# DriverIC.net
KiCad netlist of a schematic drawn in Altium Designer
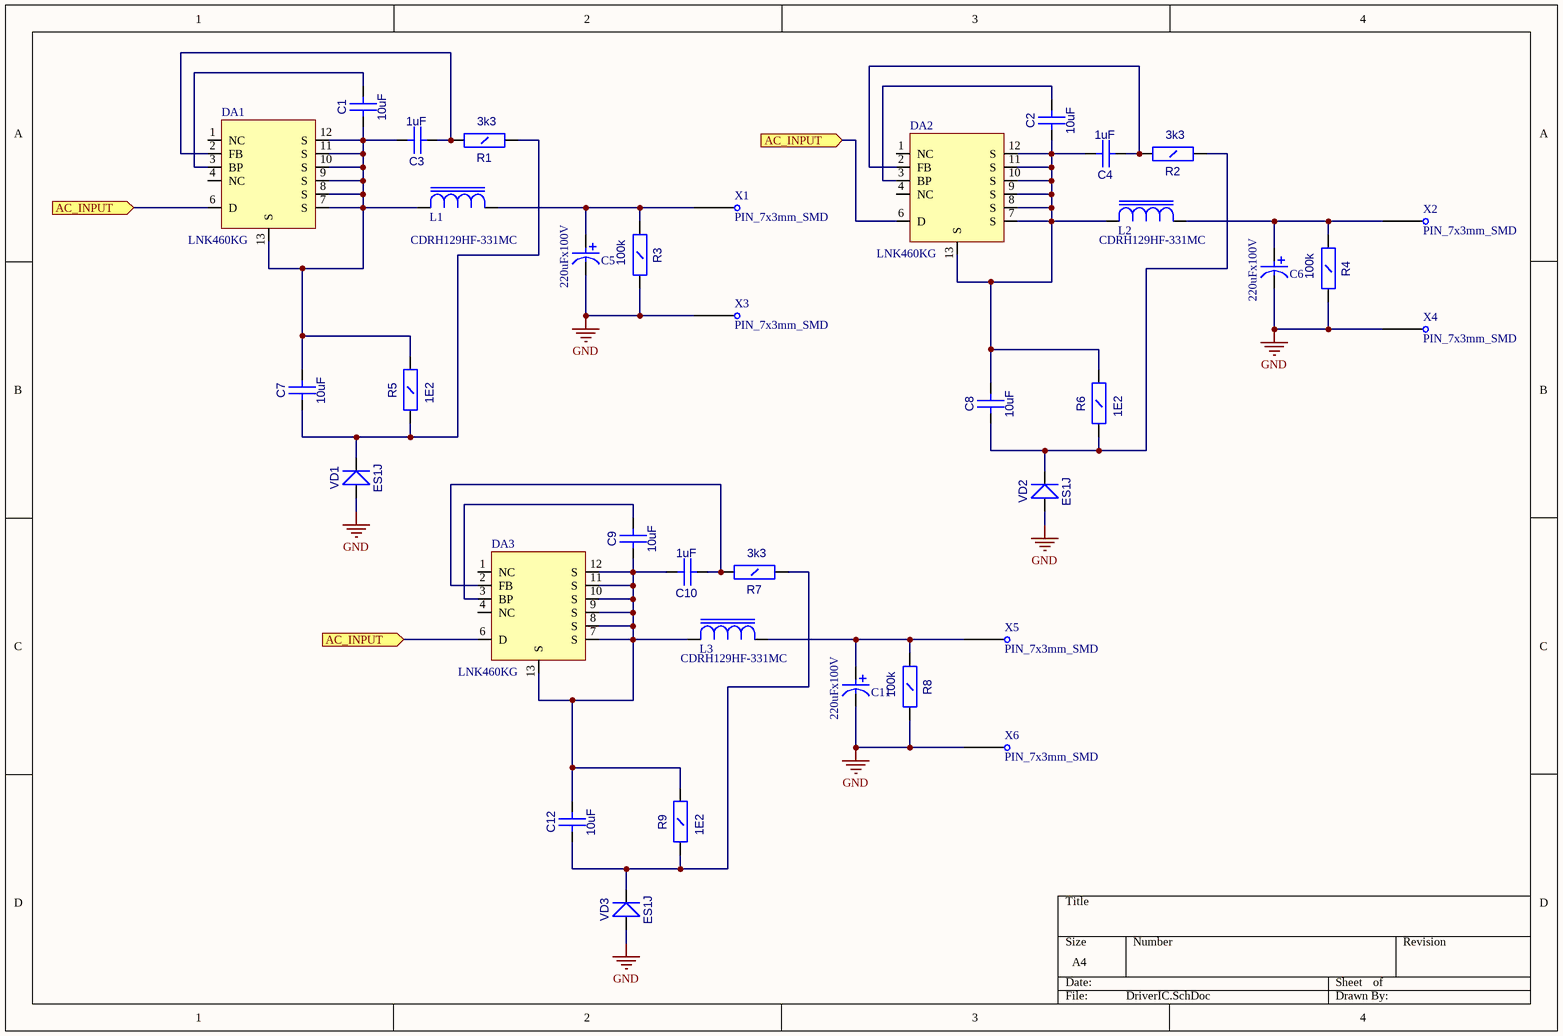
[diagram p0: DriverIC.SchDoc]

(export (version "E")
  (design (tool "Eeschema 10.0.6"))
  (components
    (comp (ref "C1")
      (value "10uF")
      (footprint "CC1206")
      (description "CC1206")
      (libsource (lib "gprs_modem_2") (part "CC1206"))
    )
    (comp (ref "C2")
      (value "10uF")
      (footprint "CC1206")
      (description "CC1206")
      (libsource (lib "gprs_modem_2") (part "CC1206"))
    )
    (comp (ref "C3")
      (value "1uF")
      (footprint "CC1206")
      (description "CC1206")
      (libsource (lib "gprs_modem_2") (part "CC1206"))
    )
    (comp (ref "C4")
      (value "1uF")
      (footprint "CC1206")
      (description "CC1206")
      (libsource (lib "gprs_modem_2") (part "CC1206"))
    )
    (comp (ref "C5")
      (value "220uFx100V")
      (footprint "CAP_16x22_2")
      (libsource (lib "gprs_modem_2") (part "CAP_16x22"))
    )
    (comp (ref "C6")
      (value "220uFx100V")
      (footprint "CAP_16x22_2")
      (libsource (lib "gprs_modem_2") (part "CAP_16x22"))
    )
    (comp (ref "C7")
      (value "10uF")
      (footprint "CC1206")
      (description "CC1206")
      (libsource (lib "gprs_modem_2") (part "CC1206"))
    )
    (comp (ref "C8")
      (value "10uF")
      (footprint "CC1206")
      (description "CC1206")
      (libsource (lib "gprs_modem_2") (part "CC1206"))
    )
    (comp (ref "C9")
      (value "10uF")
      (footprint "CC1206")
      (description "CC1206")
      (libsource (lib "gprs_modem_2") (part "CC1206"))
    )
    (comp (ref "C10")
      (value "1uF")
      (footprint "CC1206")
      (description "CC1206")
      (libsource (lib "gprs_modem_2") (part "CC1206"))
    )
    (comp (ref "C11")
      (value "220uFx100V")
      (footprint "CAP_16x22_2")
      (libsource (lib "gprs_modem_2") (part "CAP_16x22"))
    )
    (comp (ref "C12")
      (value "10uF")
      (footprint "CC1206")
      (description "CC1206")
      (libsource (lib "gprs_modem_2") (part "CC1206"))
    )
    (comp (ref "DA1")
      (value "LNK460KG")
      (footprint "eSOP-12")
      (libsource (lib "gprs_modem") (part "LNK460KG"))
    )
    (comp (ref "DA2")
      (value "LNK460KG")
      (footprint "eSOP-12")
      (libsource (lib "gprs_modem") (part "LNK460KG"))
    )
    (comp (ref "DA3")
      (value "LNK460KG")
      (footprint "eSOP-12")
      (libsource (lib "gprs_modem") (part "LNK460KG"))
    )
    (comp (ref "L1")
      (value "CDRH129HF-331MC")
      (footprint "IND_CDRH129")
      (libsource (lib "gprs_modem_2") (part "CDRH129"))
    )
    (comp (ref "L2")
      (value "CDRH129HF-331MC")
      (footprint "IND_CDRH129")
      (libsource (lib "gprs_modem_2") (part "CDRH129"))
    )
    (comp (ref "L3")
      (value "CDRH129HF-331MC")
      (footprint "IND_CDRH129")
      (libsource (lib "gprs_modem_2") (part "CDRH129"))
    )
    (comp (ref "R1")
      (value "3k3")
      (footprint "RC1206")
      (description "RC1206")
      (libsource (lib "gprs_modem_2") (part "RC1206"))
    )
    (comp (ref "R2")
      (value "3k3")
      (footprint "RC1206")
      (description "RC1206")
      (libsource (lib "gprs_modem_2") (part "RC1206"))
    )
    (comp (ref "R3")
      (value "100k")
      (footprint "RC1206")
      (description "RC1206")
      (libsource (lib "gprs_modem_2") (part "RC1206"))
    )
    (comp (ref "R4")
      (value "100k")
      (footprint "RC1206")
      (description "RC1206")
      (libsource (lib "gprs_modem_2") (part "RC1206"))
    )
    (comp (ref "R5")
      (value "1E2")
      (footprint "RC1206")
      (description "RC1206")
      (libsource (lib "gprs_modem_2") (part "RC1206"))
    )
    (comp (ref "R6")
      (value "1E2")
      (footprint "RC1206")
      (description "RC1206")
      (libsource (lib "gprs_modem_2") (part "RC1206"))
    )
    (comp (ref "R7")
      (value "3k3")
      (footprint "RC1206")
      (description "RC1206")
      (libsource (lib "gprs_modem_2") (part "RC1206"))
    )
    (comp (ref "R8")
      (value "100k")
      (footprint "RC1206")
      (description "RC1206")
      (libsource (lib "gprs_modem_2") (part "RC1206"))
    )
    (comp (ref "R9")
      (value "1E2")
      (footprint "RC1206")
      (description "RC1206")
      (libsource (lib "gprs_modem_2") (part "RC1206"))
    )
    (comp (ref "VD1")
      (value "ES1J")
      (footprint "SMA")
      (description "Schottky Rectifier")
      (libsource (lib "gprs_modem") (part "SS14"))
    )
    (comp (ref "VD2")
      (value "ES1J")
      (footprint "SMA")
      (description "Schottky Rectifier")
      (libsource (lib "gprs_modem") (part "SS14"))
    )
    (comp (ref "VD3")
      (value "ES1J")
      (footprint "SMA")
      (description "Schottky Rectifier")
      (libsource (lib "gprs_modem") (part "SS14"))
    )
    (comp (ref "X1")
      (value "PIN_7x3mm_SMD")
      (footprint "PIN_7x3mm_SMD")
      (libsource (lib "gprs_modem") (part "PIN_7x3mm_SMD"))
    )
    (comp (ref "X2")
      (value "PIN_7x3mm_SMD")
      (footprint "PIN_7x3mm_SMD")
      (libsource (lib "gprs_modem") (part "PIN_7x3mm_SMD"))
    )
    (comp (ref "X3")
      (value "PIN_7x3mm_SMD")
      (footprint "PIN_7x3mm_SMD")
      (libsource (lib "gprs_modem") (part "PIN_7x3mm_SMD"))
    )
    (comp (ref "X4")
      (value "PIN_7x3mm_SMD")
      (footprint "PIN_7x3mm_SMD")
      (libsource (lib "gprs_modem") (part "PIN_7x3mm_SMD"))
    )
    (comp (ref "X5")
      (value "PIN_7x3mm_SMD")
      (footprint "PIN_7x3mm_SMD")
      (libsource (lib "gprs_modem") (part "PIN_7x3mm_SMD"))
    )
    (comp (ref "X6")
      (value "PIN_7x3mm_SMD")
      (footprint "PIN_7x3mm_SMD")
      (libsource (lib "gprs_modem") (part "PIN_7x3mm_SMD"))
    )
  )
  (nets
    (net (code "1") (name "/AC_INPUT") (class "Default")
      (node (ref "DA1") (pin "6") (pinfunction "D_6") (pintype "passive"))
      (node (ref "DA2") (pin "6") (pinfunction "D_6") (pintype "passive"))
      (node (ref "DA3") (pin "6") (pinfunction "D_6") (pintype "passive"))
    )
    (net (code "2") (name "GND") (class "Default")
      (node (ref "C11") (pin "1") (pintype "passive"))
      (node (ref "C5") (pin "1") (pintype "passive"))
      (node (ref "C6") (pin "1") (pintype "passive"))
      (node (ref "R3") (pin "2") (pinfunction "B_2") (pintype "passive"))
      (node (ref "R4") (pin "2") (pinfunction "B_2") (pintype "passive"))
      (node (ref "R8") (pin "2") (pinfunction "B_2") (pintype "passive"))
      (node (ref "VD1") (pin "1") (pinfunction "A_1") (pintype "passive"))
      (node (ref "VD2") (pin "1") (pinfunction "A_1") (pintype "passive"))
      (node (ref "VD3") (pin "1") (pinfunction "A_1") (pintype "passive"))
      (node (ref "X3") (pin "1") (pinfunction "1_1") (pintype "passive"))
      (node (ref "X4") (pin "1") (pinfunction "1_1") (pintype "passive"))
      (node (ref "X6") (pin "1") (pinfunction "1_1") (pintype "passive"))
    )
    (net (code "3") (name "Net-(C1-A)") (class "Default")
      (node (ref "C1") (pin "1") (pinfunction "A_1") (pintype "passive"))
      (node (ref "C3") (pin "2") (pinfunction "B_2") (pintype "passive"))
      (node (ref "C7") (pin "2") (pinfunction "B_2") (pintype "passive"))
      (node (ref "DA1") (pin "10") (pinfunction "S_10") (pintype "passive"))
      (node (ref "DA1") (pin "11") (pinfunction "S_11") (pintype "passive"))
      (node (ref "DA1") (pin "12") (pinfunction "S_12") (pintype "passive"))
      (node (ref "DA1") (pin "13") (pinfunction "S_13") (pintype "passive"))
      (node (ref "DA1") (pin "7") (pinfunction "S_7") (pintype "passive"))
      (node (ref "DA1") (pin "8") (pinfunction "S_8") (pintype "passive"))
      (node (ref "DA1") (pin "9") (pinfunction "S_9") (pintype "passive"))
      (node (ref "L1") (pin "1") (pinfunction "A_1") (pintype "passive"))
      (node (ref "R5") (pin "2") (pinfunction "B_2") (pintype "passive"))
    )
    (net (code "4") (name "Net-(C1-B)") (class "Default")
      (node (ref "C1") (pin "2") (pinfunction "B_2") (pintype "passive"))
      (node (ref "DA1") (pin "3") (pinfunction "BP_3") (pintype "passive"))
    )
    (net (code "5") (name "Net-(C2-A)") (class "Default")
      (node (ref "C2") (pin "1") (pinfunction "A_1") (pintype "passive"))
      (node (ref "C4") (pin "2") (pinfunction "B_2") (pintype "passive"))
      (node (ref "C8") (pin "2") (pinfunction "B_2") (pintype "passive"))
      (node (ref "DA2") (pin "10") (pinfunction "S_10") (pintype "passive"))
      (node (ref "DA2") (pin "11") (pinfunction "S_11") (pintype "passive"))
      (node (ref "DA2") (pin "12") (pinfunction "S_12") (pintype "passive"))
      (node (ref "DA2") (pin "13") (pinfunction "S_13") (pintype "passive"))
      (node (ref "DA2") (pin "7") (pinfunction "S_7") (pintype "passive"))
      (node (ref "DA2") (pin "8") (pinfunction "S_8") (pintype "passive"))
      (node (ref "DA2") (pin "9") (pinfunction "S_9") (pintype "passive"))
      (node (ref "L2") (pin "1") (pinfunction "A_1") (pintype "passive"))
      (node (ref "R6") (pin "2") (pinfunction "B_2") (pintype "passive"))
    )
    (net (code "6") (name "Net-(C2-B)") (class "Default")
      (node (ref "C2") (pin "2") (pinfunction "B_2") (pintype "passive"))
      (node (ref "DA2") (pin "3") (pinfunction "BP_3") (pintype "passive"))
    )
    (net (code "7") (name "Net-(C3-A)") (class "Default")
      (node (ref "C3") (pin "1") (pinfunction "A_1") (pintype "passive"))
      (node (ref "DA1") (pin "2") (pinfunction "FB_2") (pintype "passive"))
      (node (ref "R1") (pin "2") (pinfunction "B_2") (pintype "passive"))
    )
    (net (code "8") (name "Net-(C4-A)") (class "Default")
      (node (ref "C4") (pin "1") (pinfunction "A_1") (pintype "passive"))
      (node (ref "DA2") (pin "2") (pinfunction "FB_2") (pintype "passive"))
      (node (ref "R2") (pin "2") (pinfunction "B_2") (pintype "passive"))
    )
    (net (code "9") (name "Net-(C7-A)") (class "Default")
      (node (ref "C7") (pin "1") (pinfunction "A_1") (pintype "passive"))
      (node (ref "R1") (pin "1") (pinfunction "A_1") (pintype "passive"))
      (node (ref "R5") (pin "1") (pinfunction "A_1") (pintype "passive"))
      (node (ref "VD1") (pin "2") (pinfunction "K_2") (pintype "passive"))
    )
    (net (code "10") (name "Net-(C8-A)") (class "Default")
      (node (ref "C8") (pin "1") (pinfunction "A_1") (pintype "passive"))
      (node (ref "R2") (pin "1") (pinfunction "A_1") (pintype "passive"))
      (node (ref "R6") (pin "1") (pinfunction "A_1") (pintype "passive"))
      (node (ref "VD2") (pin "2") (pinfunction "K_2") (pintype "passive"))
    )
    (net (code "11") (name "Net-(C9-B)") (class "Default")
      (node (ref "C9") (pin "2") (pinfunction "B_2") (pintype "passive"))
      (node (ref "DA3") (pin "3") (pinfunction "BP_3") (pintype "passive"))
    )
    (net (code "12") (name "Net-(C10-A)") (class "Default")
      (node (ref "C10") (pin "1") (pinfunction "A_1") (pintype "passive"))
      (node (ref "DA3") (pin "2") (pinfunction "FB_2") (pintype "passive"))
      (node (ref "R7") (pin "2") (pinfunction "B_2") (pintype "passive"))
    )
    (net (code "13") (name "Net-(C10-B)") (class "Default")
      (node (ref "C10") (pin "2") (pinfunction "B_2") (pintype "passive"))
      (node (ref "C12") (pin "2") (pinfunction "B_2") (pintype "passive"))
      (node (ref "C9") (pin "1") (pinfunction "A_1") (pintype "passive"))
      (node (ref "DA3") (pin "10") (pinfunction "S_10") (pintype "passive"))
      (node (ref "DA3") (pin "11") (pinfunction "S_11") (pintype "passive"))
      (node (ref "DA3") (pin "12") (pinfunction "S_12") (pintype "passive"))
      (node (ref "DA3") (pin "13") (pinfunction "S_13") (pintype "passive"))
      (node (ref "DA3") (pin "7") (pinfunction "S_7") (pintype "passive"))
      (node (ref "DA3") (pin "8") (pinfunction "S_8") (pintype "passive"))
      (node (ref "DA3") (pin "9") (pinfunction "S_9") (pintype "passive"))
      (node (ref "L3") (pin "1") (pinfunction "A_1") (pintype "passive"))
      (node (ref "R9") (pin "2") (pinfunction "B_2") (pintype "passive"))
    )
    (net (code "14") (name "Net-(C12-A)") (class "Default")
      (node (ref "C12") (pin "1") (pinfunction "A_1") (pintype "passive"))
      (node (ref "R7") (pin "1") (pinfunction "A_1") (pintype "passive"))
      (node (ref "R9") (pin "1") (pinfunction "A_1") (pintype "passive"))
      (node (ref "VD3") (pin "2") (pinfunction "K_2") (pintype "passive"))
    )
    (net (code "15") (name "Net-(L1-B)") (class "Default")
      (node (ref "C5") (pin "2") (pintype "passive"))
      (node (ref "L1") (pin "2") (pinfunction "B_2") (pintype "passive"))
      (node (ref "R3") (pin "1") (pinfunction "A_1") (pintype "passive"))
      (node (ref "X1") (pin "1") (pinfunction "1_1") (pintype "passive"))
    )
    (net (code "16") (name "Net-(L2-B)") (class "Default")
      (node (ref "C6") (pin "2") (pintype "passive"))
      (node (ref "L2") (pin "2") (pinfunction "B_2") (pintype "passive"))
      (node (ref "R4") (pin "1") (pinfunction "A_1") (pintype "passive"))
      (node (ref "X2") (pin "1") (pinfunction "1_1") (pintype "passive"))
    )
    (net (code "17") (name "Net-(L3-B)") (class "Default")
      (node (ref "C11") (pin "2") (pintype "passive"))
      (node (ref "L3") (pin "2") (pinfunction "B_2") (pintype "passive"))
      (node (ref "R8") (pin "1") (pinfunction "A_1") (pintype "passive"))
      (node (ref "X5") (pin "1") (pinfunction "1_1") (pintype "passive"))
    )
    (net (code "18") (name "unconnected-(DA1-NC-Pad1)") (class "Default")
      (node (ref "DA1") (pin "1") (pinfunction "NC_1") (pintype "passive"))
    )
    (net (code "19") (name "unconnected-(DA1-NC-Pad4)") (class "Default")
      (node (ref "DA1") (pin "4") (pinfunction "NC_4") (pintype "passive"))
    )
    (net (code "20") (name "unconnected-(DA2-NC-Pad1)") (class "Default")
      (node (ref "DA2") (pin "1") (pinfunction "NC_1") (pintype "passive"))
    )
    (net (code "21") (name "unconnected-(DA2-NC-Pad4)") (class "Default")
      (node (ref "DA2") (pin "4") (pinfunction "NC_4") (pintype "passive"))
    )
    (net (code "22") (name "unconnected-(DA3-NC-Pad1)") (class "Default")
      (node (ref "DA3") (pin "1") (pinfunction "NC_1") (pintype "passive"))
    )
    (net (code "23") (name "unconnected-(DA3-NC-Pad4)") (class "Default")
      (node (ref "DA3") (pin "4") (pinfunction "NC_4") (pintype "passive"))
    )
  )
)
